# jtag-adapter-1-1.net
KiCad netlist of a schematic drawn in EAGLE
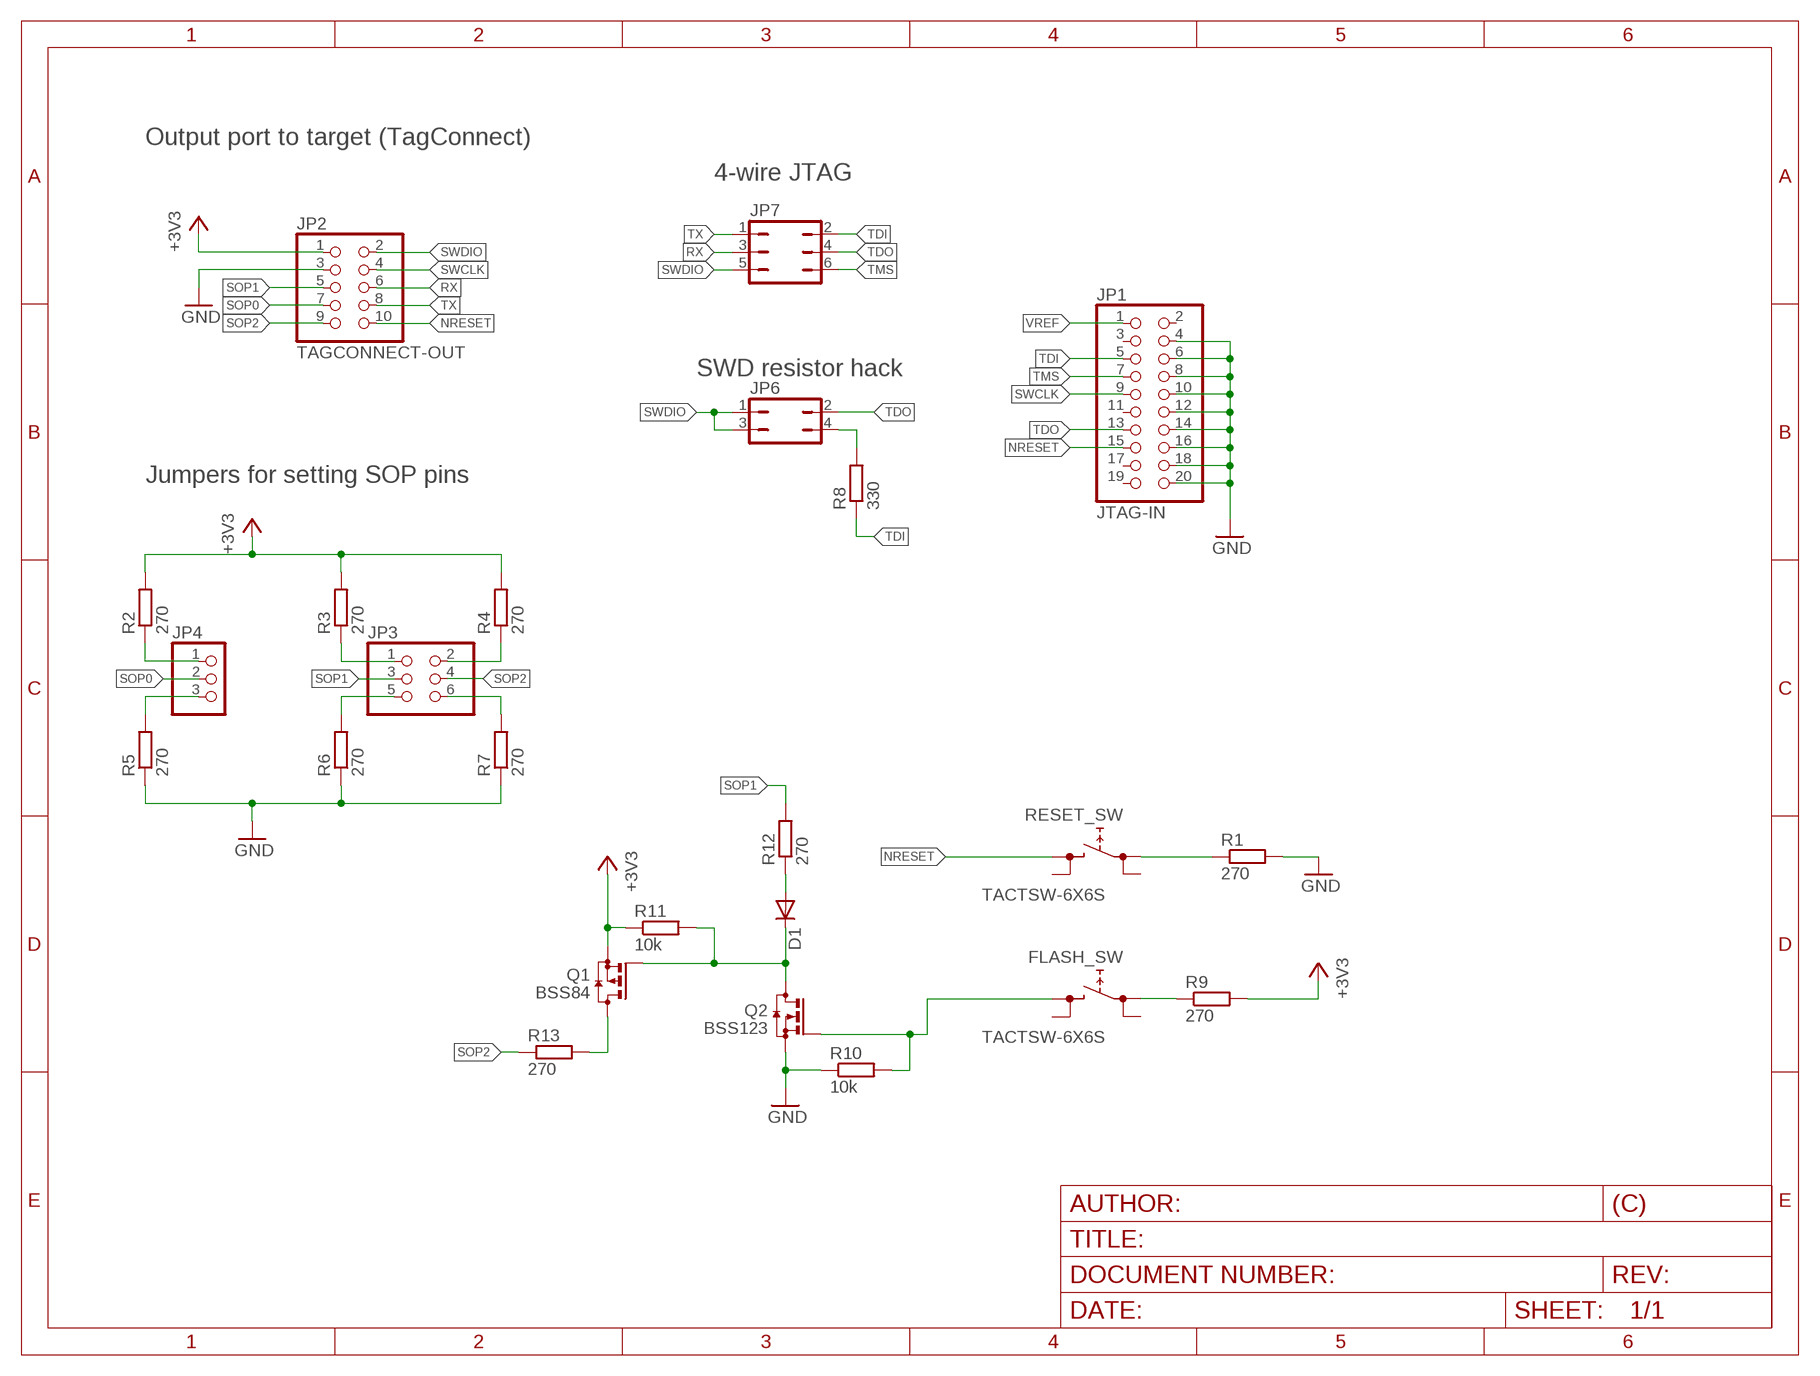
[diagram p0: schematic, sheet 1]

(export (version "E")
  (design (tool "Eeschema 10.0.6"))
  (components
    (comp (ref "D1")
      (value "DIODE-MINIMELF")
      (footprint "eagle-import:MINIMELF")
      (libsource (lib "eagle-import") (part "DIODE-MINIMELF"))
    )
    (comp (ref "FLASH_SW")
      (value "TACTSW-6X6S")
      (footprint "eagle-import:TACTSW-6X6")
      (libsource (lib "eagle-import") (part "TACTSW-6X6S"))
    )
    (comp (ref "JP1")
      (value "JTAG-IN")
      (footprint "eagle-import:2X10_90")
      (libsource (lib "eagle-import") (part "PINHD-2X10/90"))
    )
    (comp (ref "JP2")
      (value "TAGCONNECT-OUT")
      (footprint "eagle-import:CON10M")
      (libsource (lib "eagle-import") (part "PINHD-2X5CN"))
    )
    (comp (ref "JP3")
      (value "PINHD-2X3")
      (footprint "eagle-import:2X03")
      (libsource (lib "eagle-import") (part "PINHD-2X3"))
    )
    (comp (ref "JP4")
      (value "PINHD-1X3")
      (footprint "eagle-import:1X03")
      (libsource (lib "eagle-import") (part "PINHD-1X3"))
    )
    (comp (ref "JP6")
      (value "JP2Q")
      (footprint "eagle-import:JP2Q")
      (libsource (lib "eagle-import") (part "JP2Q"))
    )
    (comp (ref "JP7")
      (value "JP3Q")
      (footprint "eagle-import:JP3Q")
      (libsource (lib "eagle-import") (part "JP3Q"))
    )
    (comp (ref "Q1")
      (value "BSS84")
      (footprint "eagle-import:SOT23")
      (libsource (lib "eagle-import") (part "BSS84"))
    )
    (comp (ref "Q2")
      (value "BSS123")
      (footprint "eagle-import:SOT23")
      (libsource (lib "eagle-import") (part "BSS123"))
    )
    (comp (ref "R1")
      (value "270")
      (footprint "eagle-import:R0805")
      (libsource (lib "eagle-import") (part "R-EU_R0805"))
    )
    (comp (ref "R2")
      (value "270")
      (footprint "eagle-import:R0805")
      (libsource (lib "eagle-import") (part "R-EU_R0805"))
    )
    (comp (ref "R3")
      (value "270")
      (footprint "eagle-import:R0805")
      (libsource (lib "eagle-import") (part "R-EU_R0805"))
    )
    (comp (ref "R4")
      (value "270")
      (footprint "eagle-import:R0805")
      (libsource (lib "eagle-import") (part "R-EU_R0805"))
    )
    (comp (ref "R5")
      (value "270")
      (footprint "eagle-import:R0805")
      (libsource (lib "eagle-import") (part "R-EU_R0805"))
    )
    (comp (ref "R6")
      (value "270")
      (footprint "eagle-import:R0805")
      (libsource (lib "eagle-import") (part "R-EU_R0805"))
    )
    (comp (ref "R7")
      (value "270")
      (footprint "eagle-import:R0805")
      (libsource (lib "eagle-import") (part "R-EU_R0805"))
    )
    (comp (ref "R8")
      (value "330")
      (footprint "eagle-import:R0805")
      (libsource (lib "eagle-import") (part "R-EU_R0805"))
    )
    (comp (ref "R9")
      (value "270")
      (footprint "eagle-import:R0805")
      (libsource (lib "eagle-import") (part "R-EU_R0805"))
    )
    (comp (ref "R10")
      (value "10k")
      (footprint "eagle-import:R0805")
      (libsource (lib "eagle-import") (part "R-EU_R0805"))
    )
    (comp (ref "R11")
      (value "10k")
      (footprint "eagle-import:R0805")
      (libsource (lib "eagle-import") (part "R-EU_R0805"))
    )
    (comp (ref "R12")
      (value "270")
      (footprint "eagle-import:R0805")
      (libsource (lib "eagle-import") (part "R-EU_R0805"))
    )
    (comp (ref "R13")
      (value "270")
      (footprint "eagle-import:R0805")
      (libsource (lib "eagle-import") (part "R-EU_R0805"))
    )
    (comp (ref "RESET_SW")
      (value "TACTSW-6X6S")
      (footprint "eagle-import:TACTSW-6X6")
      (libsource (lib "eagle-import") (part "TACTSW-6X6S"))
    )
  )
  (nets
    (net (code "1") (name "+3V3") (class "Default")
      (node (ref "JP2") (pin "1") (pinfunction "1_1") (pintype "passive"))
      (node (ref "Q1") (pin "2") (pinfunction "S_2") (pintype "passive"))
      (node (ref "R11") (pin "1") (pinfunction "1_1") (pintype "passive"))
      (node (ref "R2") (pin "2") (pinfunction "2_2") (pintype "passive"))
      (node (ref "R3") (pin "2") (pinfunction "2_2") (pintype "passive"))
      (node (ref "R4") (pin "2") (pinfunction "2_2") (pintype "passive"))
      (node (ref "R9") (pin "2") (pinfunction "2_2") (pintype "passive"))
    )
    (net (code "2") (name "GND") (class "Default")
      (node (ref "JP1") (pin "10") (pinfunction "10_10") (pintype "passive"))
      (node (ref "JP1") (pin "12") (pinfunction "12_12") (pintype "passive"))
      (node (ref "JP1") (pin "14") (pinfunction "14_14") (pintype "passive"))
      (node (ref "JP1") (pin "16") (pinfunction "16_16") (pintype "passive"))
      (node (ref "JP1") (pin "18") (pinfunction "18_18") (pintype "passive"))
      (node (ref "JP1") (pin "20") (pinfunction "20_20") (pintype "passive"))
      (node (ref "JP1") (pin "4") (pinfunction "4_4") (pintype "passive"))
      (node (ref "JP1") (pin "6") (pinfunction "6_6") (pintype "passive"))
      (node (ref "JP1") (pin "8") (pinfunction "8_8") (pintype "passive"))
      (node (ref "JP2") (pin "3") (pinfunction "3_3") (pintype "passive"))
      (node (ref "Q2") (pin "2") (pinfunction "S_2") (pintype "passive"))
      (node (ref "R1") (pin "2") (pinfunction "2_2") (pintype "passive"))
      (node (ref "R10") (pin "1") (pinfunction "1_1") (pintype "passive"))
      (node (ref "R5") (pin "1") (pinfunction "1_1") (pintype "passive"))
      (node (ref "R6") (pin "1") (pinfunction "1_1") (pintype "passive"))
      (node (ref "R7") (pin "1") (pinfunction "1_1") (pintype "passive"))
    )
    (net (code "3") (name "NRESET") (class "Default")
      (node (ref "JP1") (pin "15") (pinfunction "15_15") (pintype "passive"))
      (node (ref "JP2") (pin "10") (pinfunction "10_10") (pintype "passive"))
      (node (ref "RESET_SW") (pin "3") (pinfunction "2.1_3") (pintype "passive"))
    )
    (net (code "4") (name "Net-(D1-PadA)") (class "Default")
      (node (ref "D1") (pin "A") (pinfunction "A_A") (pintype "passive"))
      (node (ref "R12") (pin "1") (pinfunction "1_1") (pintype "passive"))
    )
    (net (code "5") (name "Net-(FLASH_SW-1.1)") (class "Default")
      (node (ref "FLASH_SW") (pin "1") (pinfunction "1.1_1") (pintype "passive"))
      (node (ref "R9") (pin "1") (pinfunction "1_1") (pintype "passive"))
    )
    (net (code "6") (name "Net-(FLASH_SW-2.1)") (class "Default")
      (node (ref "FLASH_SW") (pin "3") (pinfunction "2.1_3") (pintype "passive"))
      (node (ref "Q2") (pin "1") (pinfunction "G_1") (pintype "passive"))
      (node (ref "R10") (pin "2") (pinfunction "2_2") (pintype "passive"))
    )
    (net (code "7") (name "Net-(JP3-Pad1)") (class "Default")
      (node (ref "JP3") (pin "1") (pinfunction "1_1") (pintype "passive"))
      (node (ref "R3") (pin "1") (pinfunction "1_1") (pintype "passive"))
    )
    (net (code "8") (name "Net-(JP3-Pad2)") (class "Default")
      (node (ref "JP3") (pin "2") (pinfunction "2_2") (pintype "passive"))
      (node (ref "R4") (pin "1") (pinfunction "1_1") (pintype "passive"))
    )
    (net (code "9") (name "Net-(JP3-Pad5)") (class "Default")
      (node (ref "JP3") (pin "5") (pinfunction "5_5") (pintype "passive"))
      (node (ref "R6") (pin "2") (pinfunction "2_2") (pintype "passive"))
    )
    (net (code "10") (name "Net-(JP3-Pad6)") (class "Default")
      (node (ref "JP3") (pin "6") (pinfunction "6_6") (pintype "passive"))
      (node (ref "R7") (pin "2") (pinfunction "2_2") (pintype "passive"))
    )
    (net (code "11") (name "Net-(JP4-Pad1)") (class "Default")
      (node (ref "JP4") (pin "1") (pinfunction "1_1") (pintype "passive"))
      (node (ref "R2") (pin "1") (pinfunction "1_1") (pintype "passive"))
    )
    (net (code "12") (name "Net-(JP4-Pad3)") (class "Default")
      (node (ref "JP4") (pin "3") (pinfunction "3_3") (pintype "passive"))
      (node (ref "R5") (pin "2") (pinfunction "2_2") (pintype "passive"))
    )
    (net (code "13") (name "Net-(JP6-Pad4)") (class "Default")
      (node (ref "JP6") (pin "4") (pinfunction "4_4") (pintype "passive"))
      (node (ref "R8") (pin "2") (pinfunction "2_2") (pintype "passive"))
    )
    (net (code "14") (name "Net-(Q1-D)") (class "Default")
      (node (ref "Q1") (pin "3") (pinfunction "D_3") (pintype "passive"))
      (node (ref "R13") (pin "2") (pinfunction "2_2") (pintype "passive"))
    )
    (net (code "15") (name "Net-(Q1-G)") (class "Default")
      (node (ref "D1") (pin "C") (pinfunction "C_C") (pintype "passive"))
      (node (ref "Q1") (pin "1") (pinfunction "G_1") (pintype "passive"))
      (node (ref "Q2") (pin "3") (pinfunction "D_3") (pintype "passive"))
      (node (ref "R11") (pin "2") (pinfunction "2_2") (pintype "passive"))
    )
    (net (code "16") (name "Net-(RESET_SW-1.1)") (class "Default")
      (node (ref "R1") (pin "1") (pinfunction "1_1") (pintype "passive"))
      (node (ref "RESET_SW") (pin "1") (pinfunction "1.1_1") (pintype "passive"))
    )
    (net (code "17") (name "RX") (class "Default")
      (node (ref "JP2") (pin "6") (pinfunction "6_6") (pintype "passive"))
      (node (ref "JP7") (pin "3") (pinfunction "3_3") (pintype "passive"))
    )
    (net (code "18") (name "SOP0") (class "Default")
      (node (ref "JP2") (pin "7") (pinfunction "7_7") (pintype "passive"))
      (node (ref "JP4") (pin "2") (pinfunction "2_2") (pintype "passive"))
    )
    (net (code "19") (name "SOP1") (class "Default")
      (node (ref "JP2") (pin "5") (pinfunction "5_5") (pintype "passive"))
      (node (ref "JP3") (pin "3") (pinfunction "3_3") (pintype "passive"))
      (node (ref "R12") (pin "2") (pinfunction "2_2") (pintype "passive"))
    )
    (net (code "20") (name "SOP2") (class "Default")
      (node (ref "JP2") (pin "9") (pinfunction "9_9") (pintype "passive"))
      (node (ref "JP3") (pin "4") (pinfunction "4_4") (pintype "passive"))
      (node (ref "R13") (pin "1") (pinfunction "1_1") (pintype "passive"))
    )
    (net (code "21") (name "SWCLK") (class "Default")
      (node (ref "JP1") (pin "9") (pinfunction "9_9") (pintype "passive"))
      (node (ref "JP2") (pin "4") (pinfunction "4_4") (pintype "passive"))
    )
    (net (code "22") (name "SWDIO") (class "Default")
      (node (ref "JP2") (pin "2") (pinfunction "2_2") (pintype "passive"))
      (node (ref "JP6") (pin "1") (pinfunction "1_1") (pintype "passive"))
      (node (ref "JP6") (pin "3") (pinfunction "3_3") (pintype "passive"))
      (node (ref "JP7") (pin "5") (pinfunction "5_5") (pintype "passive"))
    )
    (net (code "23") (name "TDI") (class "Default")
      (node (ref "JP1") (pin "5") (pinfunction "5_5") (pintype "passive"))
      (node (ref "JP7") (pin "2") (pinfunction "2_2") (pintype "passive"))
      (node (ref "R8") (pin "1") (pinfunction "1_1") (pintype "passive"))
    )
    (net (code "24") (name "TDO") (class "Default")
      (node (ref "JP1") (pin "13") (pinfunction "13_13") (pintype "passive"))
      (node (ref "JP6") (pin "2") (pinfunction "2_2") (pintype "passive"))
      (node (ref "JP7") (pin "4") (pinfunction "4_4") (pintype "passive"))
    )
    (net (code "25") (name "TMS") (class "Default")
      (node (ref "JP1") (pin "7") (pinfunction "7_7") (pintype "passive"))
      (node (ref "JP7") (pin "6") (pinfunction "6_6") (pintype "passive"))
    )
    (net (code "26") (name "TX") (class "Default")
      (node (ref "JP2") (pin "8") (pinfunction "8_8") (pintype "passive"))
      (node (ref "JP7") (pin "1") (pinfunction "1_1") (pintype "passive"))
    )
    (net (code "27") (name "VREF") (class "Default")
      (node (ref "JP1") (pin "1") (pinfunction "1_1") (pintype "passive"))
    )
    (net (code "28") (name "unconnected-(FLASH_SW-1.2-Pad2)") (class "Default")
      (node (ref "FLASH_SW") (pin "2") (pinfunction "1.2_2") (pintype "passive"))
    )
    (net (code "29") (name "unconnected-(FLASH_SW-2.2-Pad4)") (class "Default")
      (node (ref "FLASH_SW") (pin "4") (pinfunction "2.2_4") (pintype "passive"))
    )
    (net (code "30") (name "unconnected-(JP1-Pad2)") (class "Default")
      (node (ref "JP1") (pin "2") (pinfunction "2_2") (pintype "passive"))
    )
    (net (code "31") (name "unconnected-(JP1-Pad3)") (class "Default")
      (node (ref "JP1") (pin "3") (pinfunction "3_3") (pintype "passive"))
    )
    (net (code "32") (name "unconnected-(JP1-Pad11)") (class "Default")
      (node (ref "JP1") (pin "11") (pinfunction "11_11") (pintype "passive"))
    )
    (net (code "33") (name "unconnected-(JP1-Pad17)") (class "Default")
      (node (ref "JP1") (pin "17") (pinfunction "17_17") (pintype "passive"))
    )
    (net (code "34") (name "unconnected-(JP1-Pad19)") (class "Default")
      (node (ref "JP1") (pin "19") (pinfunction "19_19") (pintype "passive"))
    )
    (net (code "35") (name "unconnected-(RESET_SW-1.2-Pad2)") (class "Default")
      (node (ref "RESET_SW") (pin "2") (pinfunction "1.2_2") (pintype "passive"))
    )
    (net (code "36") (name "unconnected-(RESET_SW-2.2-Pad4)") (class "Default")
      (node (ref "RESET_SW") (pin "4") (pinfunction "2.2_4") (pintype "passive"))
    )
  )
)
